# atividade-02.net
KiCad netlist of a schematic drawn in EAGLE
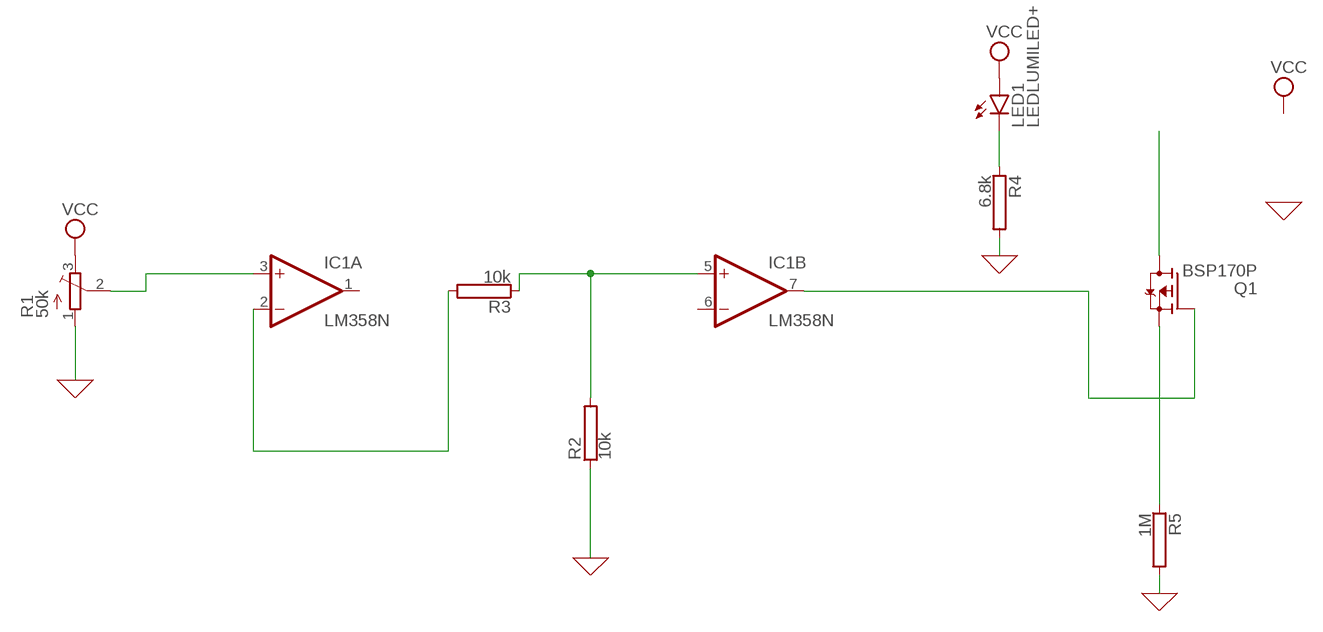
[diagram p0: schematic, sheet 1]

(export (version "E")
  (design (tool "Eeschema 10.0.6"))
  (components
    (comp (ref "IC1")
      (value "LM358N")
      (footprint "eagle-import:DIL08")
      (libsource (lib "eagle-import") (part "LM358N"))
    )
    (comp (ref "LED1")
      (value "LEDLUMILED+")
      (footprint "eagle-import:LUMILED+")
      (libsource (lib "eagle-import") (part "LEDLUMILED+"))
    )
    (comp (ref "Q1")
      (value "BSP170P")
      (footprint "eagle-import:SOT223")
      (libsource (lib "eagle-import") (part "BSP170P"))
    )
    (comp (ref "R1")
      (value "50k")
      (footprint "eagle-import:3223G")
      (libsource (lib "eagle-import") (part "TRIM_EU-3223G"))
    )
    (comp (ref "R2")
      (value "10k")
      (footprint "eagle-import:AC03")
      (libsource (lib "eagle-import") (part "RAC03"))
    )
    (comp (ref "R3")
      (value "10k")
      (footprint "eagle-import:AC03")
      (libsource (lib "eagle-import") (part "RAC03"))
    )
    (comp (ref "R4")
      (value "6.8k")
      (footprint "eagle-import:AC03")
      (libsource (lib "eagle-import") (part "RAC03"))
    )
    (comp (ref "R5")
      (value "1M")
      (footprint "eagle-import:AC03")
      (libsource (lib "eagle-import") (part "RAC03"))
    )
  )
  (nets
    (net (code "1") (name "GND") (class "Default")
      (node (ref "R1") (pin "1") (pinfunction "A_1") (pintype "passive"))
      (node (ref "R2") (pin "1") (pinfunction "1_1") (pintype "passive"))
      (node (ref "R4") (pin "2") (pinfunction "2_2") (pintype "passive"))
      (node (ref "R5") (pin "2") (pinfunction "2_2") (pintype "passive"))
    )
    (net (code "2") (name "Net-(IC1A-+IN)") (class "Default")
      (node (ref "IC1") (pin "3") (pinfunction "+IN_3") (pintype "input"))
      (node (ref "R1") (pin "2") (pinfunction "S_2") (pintype "passive"))
    )
    (net (code "3") (name "Net-(IC1A--IN)") (class "Default")
      (node (ref "IC1") (pin "2") (pinfunction "-IN_2") (pintype "input"))
      (node (ref "R3") (pin "2") (pinfunction "2_2") (pintype "passive"))
    )
    (net (code "4") (name "Net-(IC1B-+IN)") (class "Default")
      (node (ref "IC1") (pin "5") (pinfunction "+IN_5") (pintype "input"))
      (node (ref "R2") (pin "2") (pinfunction "2_2") (pintype "passive"))
      (node (ref "R3") (pin "1") (pinfunction "1_1") (pintype "passive"))
    )
    (net (code "5") (name "Net-(IC1B-OUT)") (class "Default")
      (node (ref "IC1") (pin "7") (pinfunction "OUT_7") (pintype "output"))
      (node (ref "Q1") (pin "1") (pinfunction "G_1") (pintype "passive"))
    )
    (net (code "6") (name "Net-(LED1-C)") (class "Default")
      (node (ref "LED1") (pin "4-") (pinfunction "C_4-") (pintype "passive"))
      (node (ref "R4") (pin "1") (pinfunction "1_1") (pintype "passive"))
    )
    (net (code "7") (name "Net-(Q1-D-Pad2)") (class "Default")
      (node (ref "Q1") (pin "2") (pinfunction "D_2") (pintype "passive"))
      (node (ref "Q1") (pin "4") (pinfunction "D_4") (pintype "passive"))
    )
    (net (code "8") (name "Net-(Q1-S)") (class "Default")
      (node (ref "Q1") (pin "3") (pinfunction "S_3") (pintype "passive"))
      (node (ref "R5") (pin "1") (pinfunction "1_1") (pintype "passive"))
    )
    (net (code "9") (name "VCC") (class "Default")
      (node (ref "LED1") (pin "2+") (pinfunction "A_2+") (pintype "passive"))
      (node (ref "R1") (pin "3") (pinfunction "E_3") (pintype "passive"))
    )
    (net (code "10") (name "unconnected-(IC1A-OUT-Pad1)") (class "Default")
      (node (ref "IC1") (pin "1") (pinfunction "OUT_1") (pintype "output"))
    )
    (net (code "11") (name "unconnected-(IC1B--IN-Pad6)") (class "Default")
      (node (ref "IC1") (pin "6") (pinfunction "-IN_6") (pintype "input"))
    )
  )
)
